# Sensor.net
KiCad netlist of a schematic drawn in Altium Designer
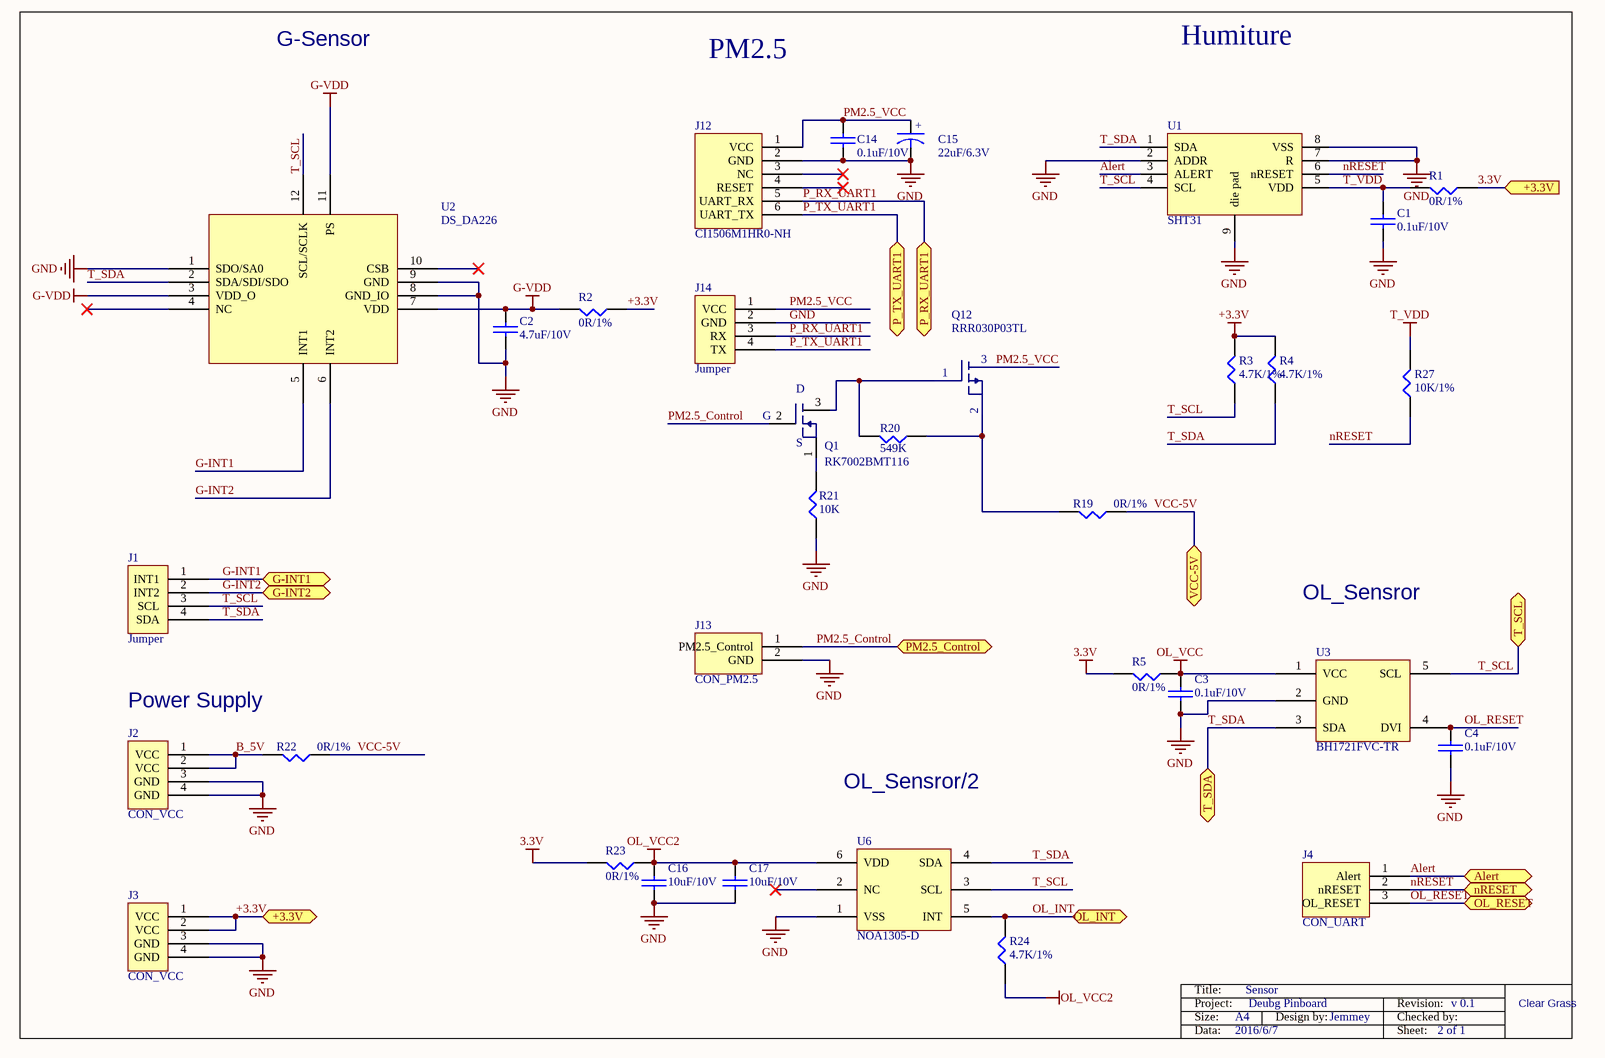
[diagram p0: Sensor.SchDoc]

(export (version "E")
  (design (tool "Eeschema 10.0.6"))
  (components
    (comp (ref "C1")
      (value "0.1uF/10V")
      (footprint "0402C")
      (description "厂家：Murata，型号：GRM155R71A104KA01D")
      (libsource (lib "*") (part "CAP"))
    )
    (comp (ref "C2")
      (value "4.7uF/10V")
      (footprint "0402C")
      (description "厂家：Murata，型号：GRM155R71A104KA01D")
      (libsource (lib "*") (part "CAP"))
    )
    (comp (ref "C3")
      (value "0.1uF/10V")
      (footprint "0402C")
      (description "厂家：Murata，型号：")
      (libsource (lib "*") (part "CAP"))
    )
    (comp (ref "C4")
      (value "0.1uF/10V")
      (footprint "0402C")
      (description "厂家：Murata，型号：")
      (libsource (lib "*") (part "CAP"))
    )
    (comp (ref "C14")
      (value "0.1uF/10V")
      (footprint "0402C")
      (description "厂家：Murata，型号：")
      (libsource (lib "*") (part "CAP"))
    )
    (comp (ref "C15")
      (value "22uF/6.3V")
      (footprint "3216")
      (description "厂家：ROHM，型号：TAJC227K010RNJ")
      (libsource (lib "MoJi LIB") (part "Capacitor"))
    )
    (comp (ref "C16")
      (value "10uF/10V")
      (footprint "0603C")
      (description "厂家：Murata，型号：")
      (libsource (lib "*") (part "CAP"))
    )
    (comp (ref "C17")
      (value "10uF/10V")
      (footprint "0603C")
      (description "厂家：Murata，型号：")
      (libsource (lib "*") (part "CAP"))
    )
    (comp (ref "J1")
      (value "Jumper")
      (footprint "2.54*4")
      (libsource (lib "Debug Pinborad_1") (part "Jumper*4"))
    )
    (comp (ref "J2")
      (value "CON_VCC")
      (footprint "2.54*4")
      (libsource (lib "Debug Pinborad_1") (part "CON_VCC"))
    )
    (comp (ref "J3")
      (value "CON_VCC")
      (footprint "2.54*4")
      (libsource (lib "Debug Pinborad_1") (part "CON_VCC"))
    )
    (comp (ref "J4")
      (value "CON_UART")
      (footprint "2.54*3")
      (libsource (lib "Debug Pinborad") (part "CON_UART"))
    )
    (comp (ref "J12")
      (value "CI1506M1HR0-NH")
      (footprint "WTB_SIDE_6PIN")
      (description "厂家：瀚荃股份，型号：CI1506M1HR0-NH")
      (libsource (lib "Bran PinBoard") (part "CI1506M1HR0-NH"))
    )
    (comp (ref "J13")
      (value "CON_PM2.5")
      (footprint "2.54*2")
      (libsource (lib "Bran PinBoard") (part "CON_PM2.5"))
    )
    (comp (ref "J14")
      (value "Jumper")
      (footprint "2.54*4")
      (libsource (lib "Bran PinBoard") (part "Jumper*4*PM25"))
    )
    (comp (ref "Q1")
      (value "RK7002BMT116")
      (footprint "SOT23")
      (description "厂家：ROHM，型号：RK7002BMT116")
      (libsource (lib "Amber") (part "RK7002BMT116"))
    )
    (comp (ref "Q12")
      (value "RRR030P03TL")
      (footprint "TSMT3")
      (description "厂家：ROHM，型号：RRR030P03TL")
      (libsource (lib "*") (part "PMOS"))
    )
    (comp (ref "R1")
      (value "0R/1%")
      (footprint "0603R")
      (description "厂家：Yageo，型号：RC0402FR-0710KL")
      (libsource (lib "*") (part "RES1"))
    )
    (comp (ref "R2")
      (value "0R/1%")
      (footprint "0603R")
      (description "厂家：Yageo，型号：RC0402FR-0710KL")
      (libsource (lib "*") (part "RES1"))
    )
    (comp (ref "R3")
      (value "4.7K/1%")
      (footprint "0402R")
      (description "厂家：Yageo，型号：RC0402FR-0710KL")
      (libsource (lib "*") (part "RES1"))
    )
    (comp (ref "R4")
      (value "4.7K/1%")
      (footprint "0402R")
      (description "厂家：Yageo，型号：RC0402FR-0710KL")
      (libsource (lib "*") (part "RES1"))
    )
    (comp (ref "R5")
      (value "0R/1%")
      (footprint "0603R")
      (description "厂家：Yageo，型号：RC0402FR-0710KL")
      (libsource (lib "*") (part "RES1"))
    )
    (comp (ref "R19")
      (value "0R/1%")
      (footprint "0603R")
      (description "厂家：Yageo，型号：RC0402FR-070RL")
      (libsource (lib "*") (part "RES1"))
    )
    (comp (ref "R20") (value "549K") (footprint "0402R") (libsource (lib "*") (part "RES1")))
    (comp (ref "R21") (value "10K") (footprint "0402R") (libsource (lib "*") (part "RES1")))
    (comp (ref "R22")
      (value "0R/1%")
      (footprint "0603R")
      (description "厂家：Yageo，型号：RC0402FR-070RL")
      (libsource (lib "*") (part "RES1"))
    )
    (comp (ref "R23")
      (value "0R/1%")
      (footprint "0603R")
      (description "厂家：Yageo，型号：RC0402FR-0710KL")
      (libsource (lib "*") (part "RES1"))
    )
    (comp (ref "R24")
      (value "4.7K/1%")
      (footprint "0402R")
      (description "厂家：Yageo，型号：RC0402FR-0710KL")
      (libsource (lib "*") (part "RES1"))
    )
    (comp (ref "R27")
      (value "10K/1%")
      (footprint "0402R")
      (description "厂家：Yageo，型号：RC0402FR-0710KL")
      (libsource (lib "*") (part "RES1"))
    )
    (comp (ref "U1")
      (value "SHT31")
      (footprint "DFN")
      (description "厂家：盛思睿，型号：SHT31")
      (libsource (lib "Temp Sensirion assy FPC") (part "SHT31"))
    )
    (comp (ref "U2")
      (value "DS_DA226")
      (footprint "LGA-12")
      (description "厂家：ST，型号：LIS2DH12")
      (libsource (lib "Debug Pinborad") (part "LIS2DE12"))
    )
    (comp (ref "U3")
      (value "BH1721FVC-TR")
      (footprint "WSOF5")
      (libsource (lib "Schlib1") (part "BH1721FVC-TR"))
    )
    (comp (ref "U6")
      (value "NOA1305-D")
      (footprint "CUDFN6")
      (libsource (lib "Bran PinBoard") (part "NOA1305-D"))
    )
  )
  (nets
    (net (code "1") (name "+3.3V") (class "Default")
      (node (ref "J3") (pin "1") (pinfunction "VCC_1") (pintype "passive"))
      (node (ref "J3") (pin "2") (pinfunction "VCC_2") (pintype "passive"))
      (node (ref "R1") (pin "1") (pinfunction "1_1") (pintype "passive"))
      (node (ref "R2") (pin "1") (pinfunction "1_1") (pintype "passive"))
      (node (ref "R23") (pin "2") (pinfunction "2_2") (pintype "passive"))
      (node (ref "R3") (pin "2") (pinfunction "2_2") (pintype "passive"))
      (node (ref "R4") (pin "2") (pinfunction "2_2") (pintype "passive"))
      (node (ref "R5") (pin "2") (pinfunction "2_2") (pintype "passive"))
    )
    (net (code "2") (name "/Alert") (class "Default")
      (node (ref "J4") (pin "1") (pinfunction "Alert_1") (pintype "passive"))
      (node (ref "U1") (pin "3") (pinfunction "ALERT_3") (pintype "passive"))
    )
    (net (code "3") (name "/B_5V") (class "Default")
      (node (ref "J2") (pin "1") (pinfunction "VCC_1") (pintype "passive"))
      (node (ref "J2") (pin "2") (pinfunction "VCC_2") (pintype "passive"))
      (node (ref "R22") (pin "2") (pinfunction "2_2") (pintype "passive"))
    )
    (net (code "4") (name "/G-INT1") (class "Default")
      (node (ref "J1") (pin "1") (pinfunction "INT1_1") (pintype "passive"))
      (node (ref "U2") (pin "5") (pinfunction "INT1_5") (pintype "passive"))
    )
    (net (code "5") (name "/G-INT2") (class "Default")
      (node (ref "J1") (pin "2") (pinfunction "INT2_2") (pintype "passive"))
      (node (ref "U2") (pin "6") (pinfunction "INT2_6") (pintype "passive"))
    )
    (net (code "6") (name "/OL_INT") (class "Default")
      (node (ref "R24") (pin "2") (pinfunction "2_2") (pintype "passive"))
      (node (ref "U6") (pin "5") (pinfunction "INT_5") (pintype "passive"))
    )
    (net (code "7") (name "/OL_RESET") (class "Default")
      (node (ref "C4") (pin "1") (pinfunction "1_1") (pintype "passive"))
      (node (ref "J4") (pin "3") (pinfunction "OL_RESET_3") (pintype "passive"))
      (node (ref "U3") (pin "4") (pinfunction "DVI_4") (pintype "passive"))
    )
    (net (code "8") (name "/PM2.5_Control") (class "Default")
      (node (ref "J13") (pin "1") (pinfunction "PM2.5_Control_1") (pintype "passive"))
      (node (ref "Q1") (pin "2") (pinfunction "G_2") (pintype "passive"))
    )
    (net (code "9") (name "/PM2.5_VCC") (class "Default")
      (node (ref "C14") (pin "1") (pinfunction "1_1") (pintype "passive"))
      (node (ref "C15") (pin "1") (pinfunction "1_1") (pintype "passive"))
      (node (ref "J12") (pin "1") (pinfunction "VCC_1") (pintype "passive"))
      (node (ref "J14") (pin "1") (pinfunction "VCC_1") (pintype "passive"))
      (node (ref "Q12") (pin "3") (pinfunction "D_3") (pintype "passive"))
    )
    (net (code "10") (name "/P_RX_UART1") (class "Default")
      (node (ref "J12") (pin "5") (pinfunction "UART_RX_5") (pintype "passive"))
      (node (ref "J14") (pin "3") (pinfunction "RX_3") (pintype "passive"))
    )
    (net (code "11") (name "/P_TX_UART1") (class "Default")
      (node (ref "J12") (pin "6") (pinfunction "UART_TX_6") (pintype "passive"))
      (node (ref "J14") (pin "4") (pinfunction "TX_4") (pintype "passive"))
    )
    (net (code "12") (name "/T_SCL") (class "Default")
      (node (ref "J1") (pin "3") (pinfunction "SCL_3") (pintype "passive"))
      (node (ref "R3") (pin "1") (pinfunction "1_1") (pintype "passive"))
      (node (ref "U1") (pin "4") (pinfunction "SCL_4") (pintype "passive"))
      (node (ref "U2") (pin "12") (pinfunction "SCL/SCLK_12") (pintype "passive"))
      (node (ref "U3") (pin "5") (pinfunction "SCL_5") (pintype "passive"))
      (node (ref "U6") (pin "3") (pinfunction "SCL_3") (pintype "passive"))
    )
    (net (code "13") (name "/T_SDA") (class "Default")
      (node (ref "J1") (pin "4") (pinfunction "SDA_4") (pintype "passive"))
      (node (ref "R4") (pin "1") (pinfunction "1_1") (pintype "passive"))
      (node (ref "U1") (pin "1") (pinfunction "SDA_1") (pintype "passive"))
      (node (ref "U2") (pin "2") (pinfunction "SDA/SDI/SDO_2") (pintype "passive"))
      (node (ref "U3") (pin "3") (pinfunction "SDA_3") (pintype "passive"))
      (node (ref "U6") (pin "4") (pinfunction "SDA_4") (pintype "passive"))
    )
    (net (code "14") (name "/VCC-5V") (class "Default")
      (node (ref "R19") (pin "1") (pinfunction "1_1") (pintype "passive"))
      (node (ref "R22") (pin "1") (pinfunction "1_1") (pintype "passive"))
    )
    (net (code "15") (name "/nRESET") (class "Default")
      (node (ref "J4") (pin "2") (pinfunction "nRESET_2") (pintype "passive"))
      (node (ref "R27") (pin "1") (pinfunction "1_1") (pintype "passive"))
      (node (ref "U1") (pin "6") (pinfunction "nRESET_6") (pintype "passive"))
    )
    (net (code "16") (name "G-VDD") (class "Default")
      (node (ref "C2") (pin "1") (pinfunction "1_1") (pintype "passive"))
      (node (ref "R2") (pin "2") (pinfunction "2_2") (pintype "passive"))
      (node (ref "U2") (pin "11") (pinfunction "PS_11") (pintype "passive"))
      (node (ref "U2") (pin "3") (pinfunction "VDD_O_3") (pintype "passive"))
      (node (ref "U2") (pin "7") (pinfunction "VDD_7") (pintype "passive"))
    )
    (net (code "17") (name "GND") (class "Default")
      (node (ref "C1") (pin "2") (pinfunction "2_2") (pintype "passive"))
      (node (ref "C14") (pin "2") (pinfunction "2_2") (pintype "passive"))
      (node (ref "C15") (pin "2") (pinfunction "2_2") (pintype "passive"))
      (node (ref "C16") (pin "2") (pinfunction "2_2") (pintype "passive"))
      (node (ref "C17") (pin "2") (pinfunction "2_2") (pintype "passive"))
      (node (ref "C2") (pin "2") (pinfunction "2_2") (pintype "passive"))
      (node (ref "C3") (pin "2") (pinfunction "2_2") (pintype "passive"))
      (node (ref "C4") (pin "2") (pinfunction "2_2") (pintype "passive"))
      (node (ref "J12") (pin "2") (pinfunction "GND_2") (pintype "passive"))
      (node (ref "J13") (pin "2") (pinfunction "GND_2") (pintype "passive"))
      (node (ref "J14") (pin "2") (pinfunction "GND_2") (pintype "passive"))
      (node (ref "J2") (pin "3") (pinfunction "GND_3") (pintype "passive"))
      (node (ref "J2") (pin "4") (pinfunction "GND_4") (pintype "passive"))
      (node (ref "J3") (pin "3") (pinfunction "GND_3") (pintype "passive"))
      (node (ref "J3") (pin "4") (pinfunction "GND_4") (pintype "passive"))
      (node (ref "R21") (pin "1") (pinfunction "1_1") (pintype "passive"))
      (node (ref "U1") (pin "2") (pinfunction "ADDR_2") (pintype "passive"))
      (node (ref "U1") (pin "7") (pinfunction "R_7") (pintype "passive"))
      (node (ref "U1") (pin "8") (pinfunction "VSS_8") (pintype "passive"))
      (node (ref "U1") (pin "9") (pinfunction "die_pad_9") (pintype "passive"))
      (node (ref "U2") (pin "1") (pinfunction "SDO/SA0_1") (pintype "passive"))
      (node (ref "U2") (pin "8") (pinfunction "GND_IO_8") (pintype "passive"))
      (node (ref "U2") (pin "9") (pinfunction "GND_9") (pintype "passive"))
      (node (ref "U3") (pin "2") (pinfunction "GND_2") (pintype "passive"))
      (node (ref "U6") (pin "1") (pinfunction "VSS_1") (pintype "passive"))
    )
    (net (code "18") (name "Net-(Q1-D)") (class "Default")
      (node (ref "Q1") (pin "3") (pinfunction "D_3") (pintype "passive"))
      (node (ref "Q12") (pin "1") (pinfunction "G_1") (pintype "passive"))
      (node (ref "R20") (pin "2") (pinfunction "2_2") (pintype "passive"))
    )
    (net (code "19") (name "Net-(Q1-S)") (class "Default")
      (node (ref "Q1") (pin "1") (pinfunction "S_1") (pintype "passive"))
      (node (ref "R21") (pin "2") (pinfunction "2_2") (pintype "passive"))
    )
    (net (code "20") (name "Net-(Q12-S)") (class "Default")
      (node (ref "Q12") (pin "2") (pinfunction "S_2") (pintype "passive"))
      (node (ref "R19") (pin "2") (pinfunction "2_2") (pintype "passive"))
      (node (ref "R20") (pin "1") (pinfunction "1_1") (pintype "passive"))
    )
    (net (code "21") (name "OL_VCC") (class "Default")
      (node (ref "C3") (pin "1") (pinfunction "1_1") (pintype "passive"))
      (node (ref "R5") (pin "1") (pinfunction "1_1") (pintype "passive"))
      (node (ref "U3") (pin "1") (pinfunction "VCC_1") (pintype "passive"))
    )
    (net (code "22") (name "OL_VCC2") (class "Default")
      (node (ref "C16") (pin "1") (pinfunction "1_1") (pintype "passive"))
      (node (ref "C17") (pin "1") (pinfunction "1_1") (pintype "passive"))
      (node (ref "R23") (pin "1") (pinfunction "1_1") (pintype "passive"))
      (node (ref "R24") (pin "1") (pinfunction "1_1") (pintype "passive"))
      (node (ref "U6") (pin "6") (pinfunction "VDD_6") (pintype "passive"))
    )
    (net (code "23") (name "T_VDD") (class "Default")
      (node (ref "C1") (pin "1") (pinfunction "1_1") (pintype "passive"))
      (node (ref "R1") (pin "2") (pinfunction "2_2") (pintype "passive"))
      (node (ref "R27") (pin "2") (pinfunction "2_2") (pintype "passive"))
      (node (ref "U1") (pin "5") (pinfunction "VDD_5") (pintype "passive"))
    )
    (net (code "24") (name "unconnected-(J12-NC-Pad3)") (class "Default")
      (node (ref "J12") (pin "3") (pinfunction "NC_3") (pintype "passive+no_connect"))
    )
    (net (code "25") (name "unconnected-(J12-RESET-Pad4)") (class "Default")
      (node (ref "J12") (pin "4") (pinfunction "RESET_4") (pintype "passive+no_connect"))
    )
    (net (code "26") (name "unconnected-(U2-CSB-Pad10)") (class "Default")
      (node (ref "U2") (pin "10") (pinfunction "CSB_10") (pintype "passive+no_connect"))
    )
    (net (code "27") (name "unconnected-(U2-NC-Pad4)") (class "Default")
      (node (ref "U2") (pin "4") (pinfunction "NC_4") (pintype "passive+no_connect"))
    )
    (net (code "28") (name "unconnected-(U6-NC-Pad2)") (class "Default")
      (node (ref "U6") (pin "2") (pinfunction "NC_2") (pintype "passive+no_connect"))
    )
  )
)
